# ignition.net
KiCad netlist of a schematic drawn in Altium Designer
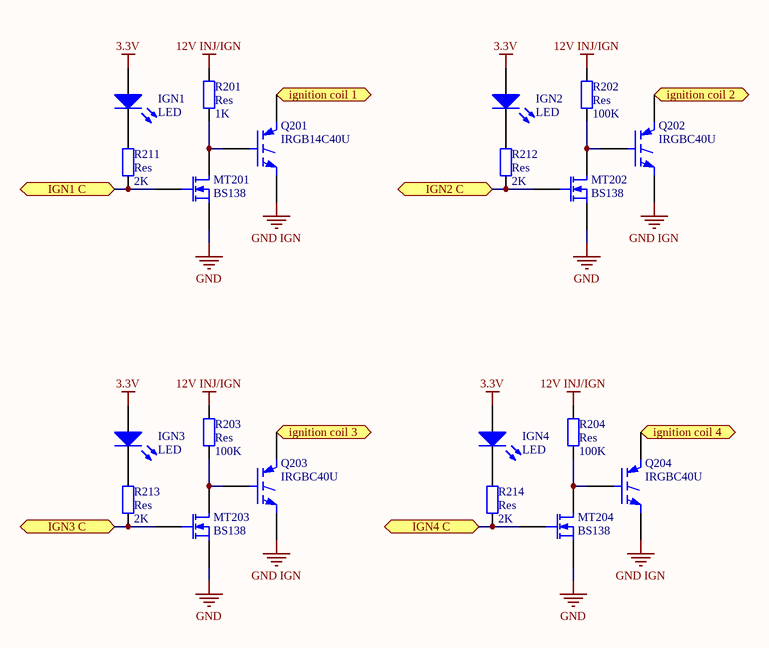
[diagram p0: ignition.SchDoc]

(export (version "E")
  (design (tool "Eeschema 10.0.6"))
  (components
    (comp (ref "IGN1") (value "LED") (footprint "LED 3mm") (libsource (lib "ArduinoNano") (part "LED")))
    (comp (ref "IGN2") (value "LED") (footprint "LED 3mm") (libsource (lib "ArduinoNano") (part "LED")))
    (comp (ref "IGN3") (value "LED") (footprint "LED 3mm") (libsource (lib "ArduinoNano") (part "LED")))
    (comp (ref "IGN4") (value "LED") (footprint "LED 3mm") (libsource (lib "ArduinoNano") (part "LED")))
    (comp (ref "MT201") (value "BS138") (footprint "SOT23") (libsource (lib "ArduinoNano") (part "BS138")))
    (comp (ref "MT202") (value "BS138") (footprint "SOT23") (libsource (lib "ArduinoNano") (part "BS138")))
    (comp (ref "MT203") (value "BS138") (footprint "SOT23") (libsource (lib "ArduinoNano") (part "BS138")))
    (comp (ref "MT204") (value "BS138") (footprint "SOT23") (libsource (lib "ArduinoNano") (part "BS138")))
    (comp (ref "Q201")
      (value "IRGB14C40U")
      (footprint "TO-220AB")
      (description "Insulated Gate Bipolar Transistor")
      (fields (field (name "PUBLISHER") "Altium Limited"))
      (libsource (lib "IR Discrete IGBT") (part "IRGBC40U"))
    )
    (comp (ref "Q202")
      (value "IRGBC40U")
      (footprint "TO-220AB")
      (description "Insulated Gate Bipolar Transistor")
      (fields (field (name "PUBLISHER") "Altium Limited"))
      (libsource (lib "IR Discrete IGBT") (part "IRGBC40U"))
    )
    (comp (ref "Q203")
      (value "IRGBC40U")
      (footprint "TO-220AB")
      (description "Insulated Gate Bipolar Transistor")
      (fields (field (name "PUBLISHER") "Altium Limited"))
      (libsource (lib "IR Discrete IGBT") (part "IRGBC40U"))
    )
    (comp (ref "Q204")
      (value "IRGBC40U")
      (footprint "TO-220AB")
      (description "Insulated Gate Bipolar Transistor")
      (fields (field (name "PUBLISHER") "Altium Limited"))
      (libsource (lib "IR Discrete IGBT") (part "IRGBC40U"))
    )
    (comp (ref "R201")
      (value "Res")
      (footprint "1206 footprint")
      (fields (field (name "ALTIUM_VALUE") "1K"))
      (libsource (lib "ArduinoNano") (part "Res"))
    )
    (comp (ref "R202")
      (value "Res")
      (footprint "1206 footprint")
      (fields (field (name "ALTIUM_VALUE") "100K"))
      (libsource (lib "ArduinoNano") (part "Res"))
    )
    (comp (ref "R203")
      (value "Res")
      (footprint "1206 footprint")
      (fields (field (name "ALTIUM_VALUE") "100K"))
      (libsource (lib "ArduinoNano") (part "Res"))
    )
    (comp (ref "R204")
      (value "Res")
      (footprint "1206 footprint")
      (fields (field (name "ALTIUM_VALUE") "100K"))
      (libsource (lib "ArduinoNano") (part "Res"))
    )
    (comp (ref "R211")
      (value "Res")
      (footprint "1206 footprint")
      (fields (field (name "ALTIUM_VALUE") "2K"))
      (libsource (lib "ArduinoNano") (part "Res"))
    )
    (comp (ref "R212")
      (value "Res")
      (footprint "1206 footprint")
      (fields (field (name "ALTIUM_VALUE") "2K"))
      (libsource (lib "ArduinoNano") (part "Res"))
    )
    (comp (ref "R213")
      (value "Res")
      (footprint "1206 footprint")
      (fields (field (name "ALTIUM_VALUE") "2K"))
      (libsource (lib "ArduinoNano") (part "Res"))
    )
    (comp (ref "R214")
      (value "Res")
      (footprint "1206 footprint")
      (fields (field (name "ALTIUM_VALUE") "2K"))
      (libsource (lib "ArduinoNano") (part "Res"))
    )
  )
  (nets
    (net (code "1") (name "/IGN1 C") (class "Default")
      (node (ref "MT201") (pin "1") (pinfunction "G_1") (pintype "passive"))
      (node (ref "R211") (pin "1") (pinfunction "1_1") (pintype "passive"))
    )
    (net (code "2") (name "/IGN2 C") (class "Default")
      (node (ref "MT202") (pin "1") (pinfunction "G_1") (pintype "passive"))
      (node (ref "R212") (pin "1") (pinfunction "1_1") (pintype "passive"))
    )
    (net (code "3") (name "/IGN3 C") (class "Default")
      (node (ref "MT203") (pin "1") (pinfunction "G_1") (pintype "passive"))
      (node (ref "R213") (pin "1") (pinfunction "1_1") (pintype "passive"))
    )
    (net (code "4") (name "/IGN4 C") (class "Default")
      (node (ref "MT204") (pin "1") (pinfunction "G_1") (pintype "passive"))
      (node (ref "R214") (pin "1") (pinfunction "1_1") (pintype "passive"))
    )
    (net (code "5") (name "/ignition coil 1") (class "Default")
      (node (ref "Q201") (pin "2") (pinfunction "C_2") (pintype "passive"))
    )
    (net (code "6") (name "/ignition coil 2") (class "Default")
      (node (ref "Q202") (pin "2") (pinfunction "C_2") (pintype "passive"))
    )
    (net (code "7") (name "/ignition coil 3") (class "Default")
      (node (ref "Q203") (pin "2") (pinfunction "C_2") (pintype "passive"))
    )
    (net (code "8") (name "/ignition coil 4") (class "Default")
      (node (ref "Q204") (pin "2") (pinfunction "C_2") (pintype "passive"))
    )
    (net (code "9") (name "3.3V") (class "Default")
      (node (ref "IGN1") (pin "1") (pinfunction "A_1") (pintype "passive"))
      (node (ref "IGN2") (pin "1") (pinfunction "A_1") (pintype "passive"))
      (node (ref "IGN3") (pin "1") (pinfunction "A_1") (pintype "passive"))
      (node (ref "IGN4") (pin "1") (pinfunction "A_1") (pintype "passive"))
    )
    (net (code "10") (name "12V INJ{slash}IGN") (class "Default")
      (node (ref "R201") (pin "2") (pinfunction "2_2") (pintype "passive"))
      (node (ref "R202") (pin "2") (pinfunction "2_2") (pintype "passive"))
      (node (ref "R203") (pin "2") (pinfunction "2_2") (pintype "passive"))
      (node (ref "R204") (pin "2") (pinfunction "2_2") (pintype "passive"))
    )
    (net (code "11") (name "GND") (class "Default")
      (node (ref "MT201") (pin "2") (pinfunction "S_2") (pintype "passive"))
      (node (ref "MT202") (pin "2") (pinfunction "S_2") (pintype "passive"))
      (node (ref "MT203") (pin "2") (pinfunction "S_2") (pintype "passive"))
      (node (ref "MT204") (pin "2") (pinfunction "S_2") (pintype "passive"))
    )
    (net (code "12") (name "GND IGN") (class "Default")
      (node (ref "Q201") (pin "3") (pinfunction "E_3") (pintype "passive"))
      (node (ref "Q202") (pin "3") (pinfunction "E_3") (pintype "passive"))
      (node (ref "Q203") (pin "3") (pinfunction "E_3") (pintype "passive"))
      (node (ref "Q204") (pin "3") (pinfunction "E_3") (pintype "passive"))
    )
    (net (code "13") (name "Net-(IGN1-K)") (class "Default")
      (node (ref "IGN1") (pin "2") (pinfunction "K_2") (pintype "passive"))
      (node (ref "R211") (pin "2") (pinfunction "2_2") (pintype "passive"))
    )
    (net (code "14") (name "Net-(IGN2-K)") (class "Default")
      (node (ref "IGN2") (pin "2") (pinfunction "K_2") (pintype "passive"))
      (node (ref "R212") (pin "2") (pinfunction "2_2") (pintype "passive"))
    )
    (net (code "15") (name "Net-(IGN3-K)") (class "Default")
      (node (ref "IGN3") (pin "2") (pinfunction "K_2") (pintype "passive"))
      (node (ref "R213") (pin "2") (pinfunction "2_2") (pintype "passive"))
    )
    (net (code "16") (name "Net-(IGN4-K)") (class "Default")
      (node (ref "IGN4") (pin "2") (pinfunction "K_2") (pintype "passive"))
      (node (ref "R214") (pin "2") (pinfunction "2_2") (pintype "passive"))
    )
    (net (code "17") (name "Net-(MT201-D)") (class "Default")
      (node (ref "MT201") (pin "3") (pinfunction "D_3") (pintype "passive"))
      (node (ref "Q201") (pin "1") (pinfunction "G_1") (pintype "passive"))
      (node (ref "R201") (pin "1") (pinfunction "1_1") (pintype "passive"))
    )
    (net (code "18") (name "Net-(MT202-D)") (class "Default")
      (node (ref "MT202") (pin "3") (pinfunction "D_3") (pintype "passive"))
      (node (ref "Q202") (pin "1") (pinfunction "G_1") (pintype "passive"))
      (node (ref "R202") (pin "1") (pinfunction "1_1") (pintype "passive"))
    )
    (net (code "19") (name "Net-(MT203-D)") (class "Default")
      (node (ref "MT203") (pin "3") (pinfunction "D_3") (pintype "passive"))
      (node (ref "Q203") (pin "1") (pinfunction "G_1") (pintype "passive"))
      (node (ref "R203") (pin "1") (pinfunction "1_1") (pintype "passive"))
    )
    (net (code "20") (name "Net-(MT204-D)") (class "Default")
      (node (ref "MT204") (pin "3") (pinfunction "D_3") (pintype "passive"))
      (node (ref "Q204") (pin "1") (pinfunction "G_1") (pintype "passive"))
      (node (ref "R204") (pin "1") (pinfunction "1_1") (pintype "passive"))
    )
  )
)
